# clock_led_dual_switch.net
KiCad netlist of a schematic drawn in Altium Designer
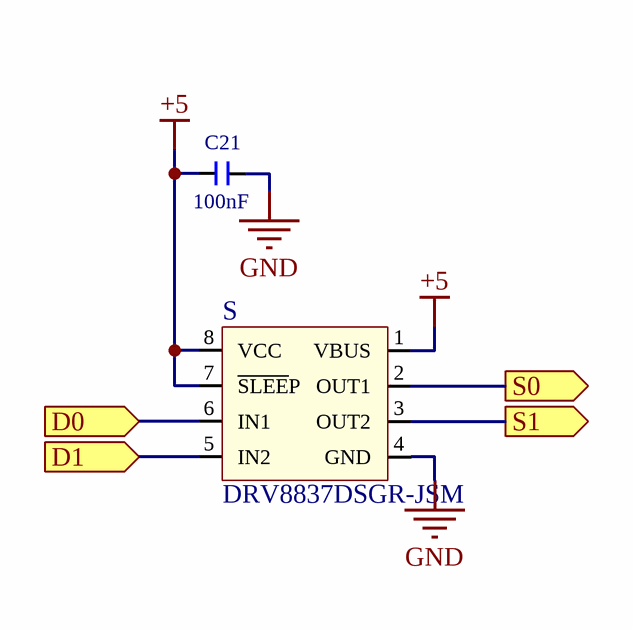
[diagram p0: clock_led_dual_switch.SchDoc]

(export (version "E")
  (design (tool "Eeschema 10.0.6"))
  (components
    (comp (ref "C21")
      (value "100nF")
      (footprint "CAP_0402")
      (description "Ceramic capacitor 0402")
      (libsource (lib "clock_led") (part "CAP_0402_100nF"))
    )
    (comp (ref "S")
      (value "DRV8837DSGR-JSM")
      (footprint "DFN-8-2x2-TP")
      (libsource (lib "clock_led") (part "DRV8837DSGR-JSM"))
    )
  )
  (nets
    (net (code "1") (name "+5") (class "Default")
      (node (ref "C21") (pin "1") (pinfunction "1_1") (pintype "passive"))
      (node (ref "S") (pin "1") (pinfunction "VBUS_1") (pintype "passive"))
      (node (ref "S") (pin "7") (pinfunction "~{SLEE}P_7") (pintype "passive"))
      (node (ref "S") (pin "8") (pinfunction "VCC_8") (pintype "passive"))
    )
    (net (code "2") (name "/D0") (class "Default")
      (node (ref "S") (pin "6") (pinfunction "IN1_6") (pintype "input"))
    )
    (net (code "3") (name "/D1") (class "Default")
      (node (ref "S") (pin "5") (pinfunction "IN2_5") (pintype "input"))
    )
    (net (code "4") (name "/S0") (class "Default")
      (node (ref "S") (pin "2") (pinfunction "OUT1_2") (pintype "output"))
    )
    (net (code "5") (name "/S1") (class "Default")
      (node (ref "S") (pin "3") (pinfunction "OUT2_3") (pintype "output"))
    )
    (net (code "6") (name "GND") (class "Default")
      (node (ref "C21") (pin "2") (pinfunction "2_2") (pintype "passive"))
      (node (ref "S") (pin "4") (pinfunction "GND_4") (pintype "passive"))
    )
  )
)
